# GoodBoy_V1_nRF9160dk_MCU_LTE.net
KiCad netlist of a schematic drawn in Altium Designer
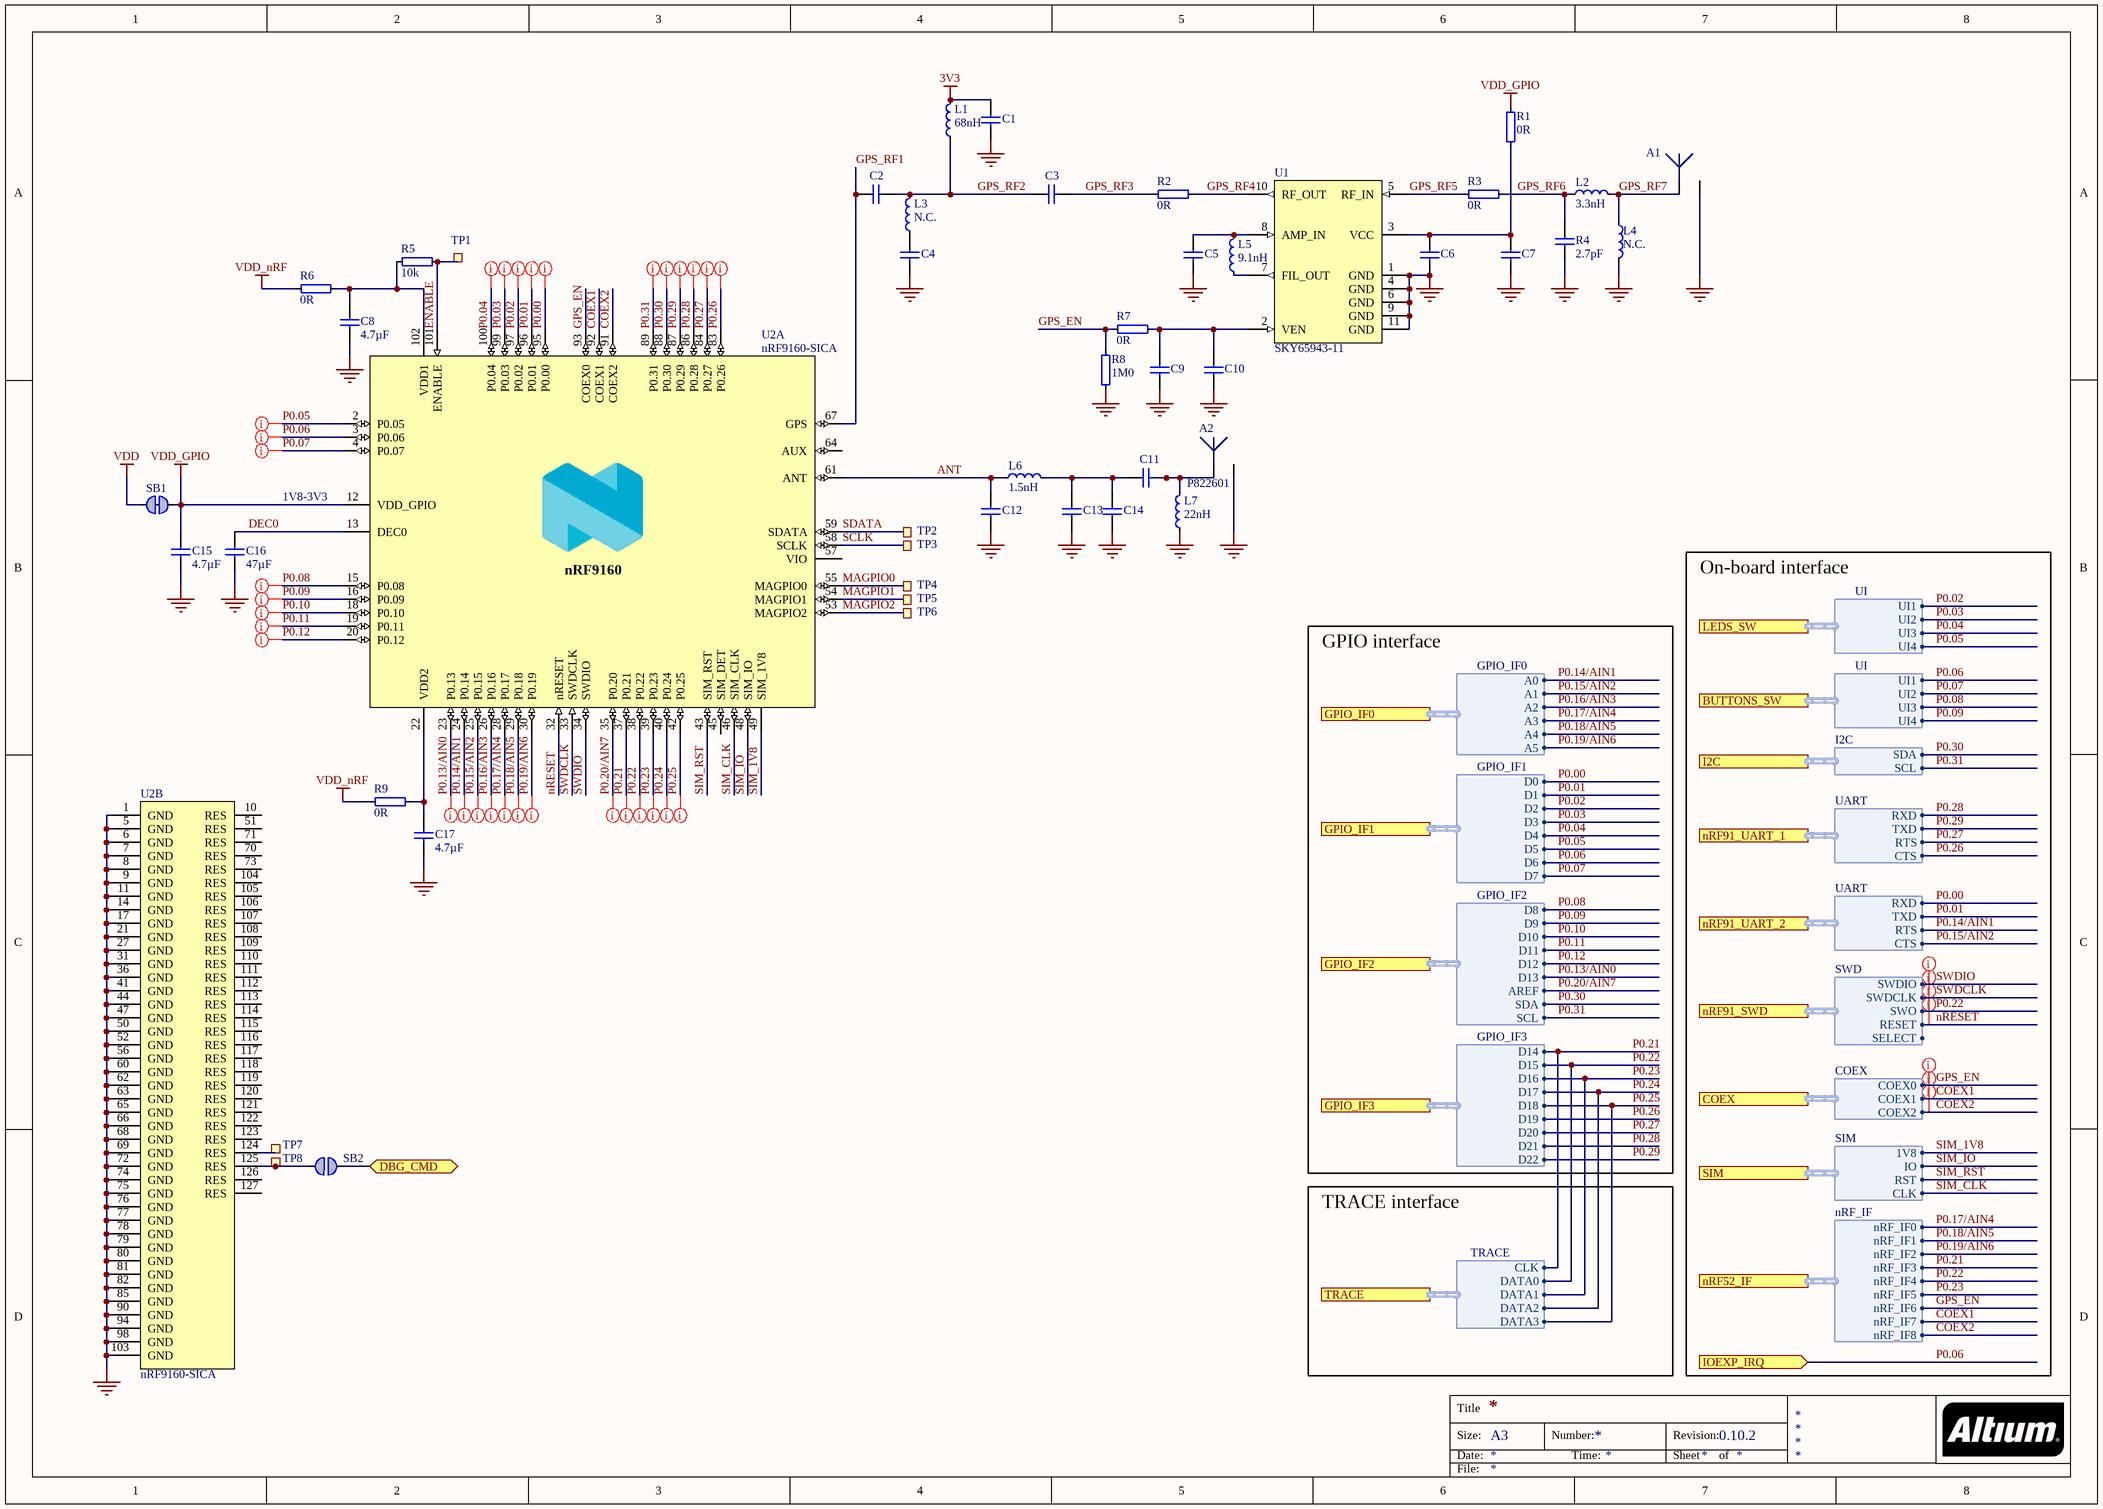
[diagram p0: GoodBoy_V1_nRF9160dk_MCU_LTE.SchDoc]

(export (version "E")
  (design (tool "Eeschema 10.0.6"))
  (components
    (comp (ref "A1")
      (value "~")
      (footprint "ACAG0301-1575-T")
      (description "RF ANT 1.575GHZ CHIP SOLDER SMD")
      (fields
        (field (name "PART NUMBER") "ACAG0301-1575-T")
        (field (name "MANUFACTURER") "Abracon")
        (field (name "PUBLISHER") "Nordic Semiconductor")
      )
      (libsource (lib "pca10090") (part "ACAG0301-1575-T"))
    )
    (comp (ref "A2")
      (value "P822601")
      (footprint "P822601")
      (description "ANTENNA PRESTTA OCTABAND LTE")
      (fields (field (name "MANUFACTURER") "Ethertronics") (field (name "PUBLISHER") "Nordic Semiconductor"))
      (libsource (lib "pca10090") (part "W3796"))
    )
    (comp (ref "C1")
      (value "~")
      (footprint "CAPC0603X03L_C")
      (description "Capacitor, NP0, ±1%, 25V")
      (fields (field (name "PART NUMBER") "C0201-39p") (field (name "PUBLISHER") "Nordic Semiconductor"))
      (libsource (lib "400389") (part "CAP"))
    )
    (comp (ref "C2")
      (value "~")
      (footprint "CAPC0603X03L_C")
      (description "Capacitor, NP0, ±1%, 25V")
      (fields (field (name "PART NUMBER") "C0201-39p") (field (name "PUBLISHER") "Nordic Semiconductor"))
      (libsource (lib "400389") (part "CAP"))
    )
    (comp (ref "C3")
      (value "~")
      (footprint "CAPC0603X03L_C")
      (description "Capacitor, NP0, ±1%, 25V")
      (fields (field (name "PART NUMBER") "C0201-39p") (field (name "PUBLISHER") "Nordic Semiconductor"))
      (libsource (lib "400389") (part "CAP"))
    )
    (comp (ref "C4")
      (value "~")
      (footprint "CAPC0603X03L_C")
      (description "Not mounted")
      (fields (field (name "PART NUMBER") "C0201-N.C.") (field (name "PUBLISHER") "Nordic Semiconductor"))
      (libsource (lib "400389") (part "CAP"))
    )
    (comp (ref "C5")
      (value "~")
      (footprint "CAPC0603X03L_C")
      (description "Not mounted")
      (fields (field (name "PART NUMBER") "C0201-N.C.") (field (name "PUBLISHER") "Nordic Semiconductor"))
      (libsource (lib "400389") (part "CAP"))
    )
    (comp (ref "C6")
      (value "~")
      (footprint "CAPC0603X03L_C")
      (description "Capacitor, NP0, ±2%, 25V")
      (fields (field (name "PART NUMBER") "C0201-100p") (field (name "PUBLISHER") "Nordic Semiconductor"))
      (libsource (lib "400389") (part "CAP"))
    )
    (comp (ref "C7")
      (value "~")
      (footprint "CAPC0603X03L_C")
      (description "Capacitor, X5R, ±10%")
      (fields (field (name "PART NUMBER") "C0201-100n") (field (name "PUBLISHER") "Nordic Semiconductor"))
      (libsource (lib "400389") (part "CAP"))
    )
    (comp (ref "C8")
      (value "4.7µF")
      (footprint "CAPC1005X04L")
      (description "Capacitor, X5R, ±20%")
      (fields (field (name "PART NUMBER") "C0402-4µ7") (field (name "PUBLISHER") "Nordic Semiconductor"))
      (libsource (lib "Nordic Passive DB") (part "CAP"))
    )
    (comp (ref "C9")
      (value "~")
      (footprint "CAPC0603X03L_C")
      (description "Capacitor, X5R, ±10%")
      (fields (field (name "PART NUMBER") "C0201-100n") (field (name "PUBLISHER") "Nordic Semiconductor"))
      (libsource (lib "400389") (part "CAP"))
    )
    (comp (ref "C10")
      (value "~")
      (footprint "CAPC0603X03L_C")
      (description "Capacitor, NP0, ±2%, 25V")
      (fields (field (name "PART NUMBER") "C0201-100p") (field (name "PUBLISHER") "Nordic Semiconductor"))
      (libsource (lib "400389") (part "CAP"))
    )
    (comp (ref "C11")
      (value "~")
      (footprint "CAPC0603X03L_C")
      (description "Capacitor, NP0, ±0.1pF, 25V")
      (fields
        (field (name "PART NUMBER") "C0201-3.5p")
        (field (name "MANUFACTURER") "Murata")
        (field (name "PUBLISHER") "Nordic Semiconductor")
      )
      (libsource (lib "400389") (part "CAP"))
    )
    (comp (ref "C12")
      (value "~")
      (footprint "CAPC0603X03L_C")
      (description "Not mounted")
      (fields (field (name "PART NUMBER") "C0201-N.C.") (field (name "PUBLISHER") "Nordic Semiconductor"))
      (libsource (lib "400389") (part "CAP"))
    )
    (comp (ref "C13")
      (value "~")
      (footprint "CAPC0603X03L_C")
      (description "Not mounted")
      (fields (field (name "PART NUMBER") "C0201-N.C.") (field (name "PUBLISHER") "Nordic Semiconductor"))
      (libsource (lib "400389") (part "CAP"))
    )
    (comp (ref "C14")
      (value "~")
      (footprint "CAPC0603X03L_C")
      (description "Not mounted")
      (fields (field (name "PART NUMBER") "C0201-N.C.") (field (name "PUBLISHER") "Nordic Semiconductor"))
      (libsource (lib "400389") (part "CAP"))
    )
    (comp (ref "C15")
      (value "4.7µF")
      (footprint "CAPC1005X04L")
      (description "Capacitor, X5R, ±20%")
      (fields (field (name "PART NUMBER") "C0402-4µ7") (field (name "PUBLISHER") "Nordic Semiconductor"))
      (libsource (lib "Nordic Passive DB") (part "CAP"))
    )
    (comp (ref "C16")
      (value "47µF")
      (footprint "CAPC2012X11L")
      (description "Capacitor, X5R, ±20%, 6.3V")
      (fields
        (field (name "PART NUMBER") "C0805-47µ")
        (field (name "MANUFACTURER") "Taiyo Yuden")
        (field (name "PUBLISHER") "Nordic Semiconductor")
      )
      (libsource (lib "Nordic Passive DB") (part "CAP"))
    )
    (comp (ref "C17")
      (value "4.7µF")
      (footprint "CAPC1005X04L")
      (description "Capacitor, X5R, ±20%")
      (fields (field (name "PART NUMBER") "C0402-4µ7") (field (name "PUBLISHER") "Nordic Semiconductor"))
      (libsource (lib "Nordic Passive DB") (part "CAP"))
    )
    (comp (ref "L1")
      (value "68nH")
      (footprint "INDC1005X04L_WW")
      (description "Inductor, 140mA, ±2%, 1960mΩ, Q=20")
      (fields
        (field (name "PART NUMBER") "L0402-68n-Wirewound-Murata")
        (field (name "MANUFACTURER") "Murata")
        (field (name "PUBLISHER") "Nordic Semiconductor")
      )
      (libsource (lib "") (part "IND_1"))
    )
    (comp (ref "L2")
      (value "3.3nH")
      (footprint "INDC1005X04L_WW")
      (description "Inductor, 900mA, ±0.5nH, 40mΩ, Q=30")
      (fields
        (field (name "PART NUMBER") "L0402-3n3-Wirewound-Murata")
        (field (name "MANUFACTURER") "Murata")
        (field (name "PUBLISHER") "Nordic Semiconductor")
      )
      (libsource (lib "Nordic Passive DB") (part "IND"))
    )
    (comp (ref "L3")
      (value "N.C.")
      (footprint "INDC1005X04L")
      (description "Not mounted")
      (fields (field (name "PART NUMBER") "L0402-N.C.") (field (name "PUBLISHER") "Nordic Semiconductor"))
      (libsource (lib "") (part "IND_1"))
    )
    (comp (ref "L4")
      (value "N.C.")
      (footprint "INDC1005X04L")
      (description "Not mounted")
      (fields (field (name "PART NUMBER") "L0402-N.C.") (field (name "PUBLISHER") "Nordic Semiconductor"))
      (libsource (lib "Nordic Passive DB") (part "IND"))
    )
    (comp (ref "L5")
      (value "9.1nH")
      (footprint "INDC1005X04L_WW")
      (description "Inductor, 540mA, ±2%, 140mΩ, Q=25")
      (fields
        (field (name "PART NUMBER") "L0402-9n1-Wirewound-Murata")
        (field (name "MANUFACTURER") "Murata")
        (field (name "PUBLISHER") "Nordic Semiconductor")
      )
      (libsource (lib "") (part "IND_1"))
    )
    (comp (ref "L6")
      (value "1.5nH")
      (footprint "INDC0603X03L_C")
      (description "Inductor, 650mA, ±0.1nH")
      (fields
        (field (name "PART NUMBER") "L0201-1n5")
        (field (name "MANUFACTURER") "Murata")
        (field (name "PUBLISHER") "Nordic Semiconductor")
      )
      (libsource (lib "Nordic Passive DB") (part "IND"))
    )
    (comp (ref "L7")
      (value "22nH")
      (footprint "INDC0603X03L_C")
      (description "Chip Inductor")
      (fields (field (name "PART NUMBER") "L0201-22n") (field (name "PUBLISHER") "Nordic Semiconductor"))
      (libsource (lib "Nordic Passive DB") (part "IND"))
    )
    (comp (ref "R1")
      (value "0R")
      (footprint "RESC0603X03L_C")
      (description "Resistor, ±5%, 0.05W")
      (fields (field (name "PART NUMBER") "R0201-0R") (field (name "PUBLISHER") "Nordic Semiconductor"))
      (libsource (lib "Nordic Passive DB") (part "RES_1"))
    )
    (comp (ref "R2")
      (value "0R")
      (footprint "RESC0603X03L_C")
      (description "Resistor, ±5%, 0.05W")
      (fields (field (name "PART NUMBER") "R0201-0R") (field (name "PUBLISHER") "Nordic Semiconductor"))
      (libsource (lib "Nordic Passive DB") (part "RES_1"))
    )
    (comp (ref "R3")
      (value "0R")
      (footprint "RESC0603X03L_C")
      (description "Resistor, ±5%, 0.05W")
      (fields (field (name "PART NUMBER") "R0201-0R") (field (name "PUBLISHER") "Nordic Semiconductor"))
      (libsource (lib "Nordic Passive DB") (part "RES_1"))
    )
    (comp (ref "R4")
      (value "2.7pF")
      (footprint "CAPC1005X04L")
      (description "Chip Cap 0402")
      (fields (field (name "PART NUMBER") "C0402-2.7p") (field (name "PUBLISHER") "Nordic Semiconductor"))
      (libsource (lib "Nordic Passive DB") (part "CAP"))
    )
    (comp (ref "R5")
      (value "10k")
      (footprint "RESC0603X03L_C")
      (description "Resistor, ±1%, 0.05W")
      (fields (field (name "PART NUMBER") "R0201-10k") (field (name "PUBLISHER") "Nordic Semiconductor"))
      (libsource (lib "Nordic Passive DB") (part "RES_1"))
    )
    (comp (ref "R6")
      (value "0R")
      (footprint "RESC0603X03L_C")
      (description "Resistor, ±5%, 0.05W")
      (fields (field (name "PART NUMBER") "R0201-0R") (field (name "PUBLISHER") "Nordic Semiconductor"))
      (libsource (lib "Nordic Passive DB") (part "RES_1"))
    )
    (comp (ref "R7")
      (value "0R")
      (footprint "RESC0603X03L_C")
      (description "Resistor, ±5%, 0.05W")
      (fields (field (name "PART NUMBER") "R0201-0R") (field (name "PUBLISHER") "Nordic Semiconductor"))
      (libsource (lib "Nordic Passive DB") (part "RES_1"))
    )
    (comp (ref "R8")
      (value "1M0")
      (footprint "RESC0603X03L_C")
      (description "Resistor, ±1%, 0.05W")
      (fields (field (name "PART NUMBER") "R0201-1M0") (field (name "PUBLISHER") "Nordic Semiconductor"))
      (libsource (lib "Nordic Passive DB") (part "RES_1"))
    )
    (comp (ref "R9")
      (value "0R")
      (footprint "RESC0603X03L_C")
      (description "Resistor, ±5%, 0.05W")
      (fields (field (name "PART NUMBER") "R0201-0R") (field (name "PUBLISHER") "Nordic Semiconductor"))
      (libsource (lib "Nordic Passive DB") (part "RES_1"))
    )
    (comp (ref "SB1")
      (value "Solderbridge")
      (footprint "Solderbridge_Shorted")
      (description "Shorted Solderbridge")
      (fields
        (field (name "PART NUMBER") "Solderbridge Shorted")
        (field (name "PUBLISHER") "Nordic Semiconductor")
      )
      (libsource (lib "Nordic Passive DB") (part "SOLDERBRIDGE_SHORTED"))
    )
    (comp (ref "SB2")
      (value "Solderbridge")
      (footprint "Solderbridge")
      (fields (field (name "PUBLISHER") "Nordic Semiconductor"))
      (libsource (lib "Nordic Passive DB") (part "SOLDERBRIDGE"))
    )
    (comp (ref "TP1")
      (value "Ø1.5mm,SMD")
      (footprint "TP_SMD_Ø1.5mm")
      (description "1.0mm circular SMD testpad")
      (fields
        (field (name "PART NUMBER") "TP_SMD_Ø1.5MM")
        (field (name "MANUFACTURER") "Nordic Semiconductor")
        (field (name "PUBLISHER") "Nordic Semiconductor")
      )
      (libsource (lib "Nordic Passive DB") (part "TESTPAD"))
    )
    (comp (ref "TP2")
      (value "Ø1.0mm,SMD")
      (footprint "TP_SMD_Ø1.0mm")
      (description "1.0mm circular SMD testpad")
      (fields
        (field (name "PART NUMBER") "TP_SMD_Ø1.0MM")
        (field (name "MANUFACTURER") "Nordic Semiconductor")
        (field (name "PUBLISHER") "Nordic Semiconductor")
      )
      (libsource (lib "") (part "TESTPAD_1"))
    )
    (comp (ref "TP3")
      (value "Ø1.0mm,SMD")
      (footprint "TP_SMD_Ø1.0mm")
      (description "1.0mm circular SMD testpad")
      (fields
        (field (name "PART NUMBER") "TP_SMD_Ø1.0MM")
        (field (name "MANUFACTURER") "Nordic Semiconductor")
        (field (name "PUBLISHER") "Nordic Semiconductor")
      )
      (libsource (lib "") (part "TESTPAD_1"))
    )
    (comp (ref "TP4")
      (value "Ø1.0mm,SMD")
      (footprint "TP_SMD_Ø1.0mm")
      (description "1.0mm circular SMD testpad")
      (fields
        (field (name "PART NUMBER") "TP_SMD_Ø1.0MM")
        (field (name "MANUFACTURER") "Nordic Semiconductor")
        (field (name "PUBLISHER") "Nordic Semiconductor")
      )
      (libsource (lib "") (part "TESTPAD_1"))
    )
    (comp (ref "TP5")
      (value "Ø1.0mm,SMD")
      (footprint "TP_SMD_Ø1.0mm")
      (description "1.0mm circular SMD testpad")
      (fields
        (field (name "PART NUMBER") "TP_SMD_Ø1.0MM")
        (field (name "MANUFACTURER") "Nordic Semiconductor")
        (field (name "PUBLISHER") "Nordic Semiconductor")
      )
      (libsource (lib "") (part "TESTPAD_1"))
    )
    (comp (ref "TP6")
      (value "Ø1.0mm,SMD")
      (footprint "TP_SMD_Ø1.0mm")
      (description "1.0mm circular SMD testpad")
      (fields
        (field (name "PART NUMBER") "TP_SMD_Ø1.0MM")
        (field (name "MANUFACTURER") "Nordic Semiconductor")
        (field (name "PUBLISHER") "Nordic Semiconductor")
      )
      (libsource (lib "") (part "TESTPAD_1"))
    )
    (comp (ref "TP7")
      (value "Ø1.0mm,SMD")
      (footprint "TP_SMD_Ø1.0mm")
      (description "1.0mm circular SMD testpad")
      (fields
        (field (name "PART NUMBER") "TP_SMD_Ø1.0MM")
        (field (name "MANUFACTURER") "Nordic Semiconductor")
        (field (name "PUBLISHER") "Nordic Semiconductor")
      )
      (libsource (lib "Nordic Passive DB") (part "TESTPAD"))
    )
    (comp (ref "TP8")
      (value "Ø1.0mm,SMD")
      (footprint "TP_SMD_Ø1.0mm")
      (description "1.0mm circular SMD testpad")
      (fields
        (field (name "PART NUMBER") "TP_SMD_Ø1.0MM")
        (field (name "MANUFACTURER") "Nordic Semiconductor")
        (field (name "PUBLISHER") "Nordic Semiconductor")
      )
      (libsource (lib "Nordic Passive DB") (part "TESTPAD"))
    )
    (comp (ref "U1")
      (value "SKY65943-11")
      (footprint "SKY65943-11")
      (description "GNSS Low-Noise Amplifier Front-End Module with Integrated Pre-Filter and Post-Filter")
      (fields (field (name "MANUFACTURER") "Skyworks") (field (name "PUBLISHER") "Nordic Semiconductor"))
      (libsource (lib "pca10090") (part "SKY65943-11"))
    )
    (comp (ref "U2")
      (value "nRF9160-SICA")
      (footprint "LGA50P1600X1050X104-161N")
      (description "Low power System-in-Package with integrated LTE-M/NB-IoT modem and GPS")
      (fields
        (field (name "PART NUMBER") "nRF9160-SICAB00")
        (field (name "MANUFACTURER") "Nordic Semiconductor")
        (field (name "PUBLISHER") "Nordic Semiconductor")
      )
      (libsource (lib "pca10090") (part "nRF9160_SICA"))
    )
  )
  (nets
    (net (code "13") (name "/ANT") (class "Default")
      (node (ref "C12") (pin "2") (pinfunction "2_2") (pintype "passive"))
      (node (ref "L6") (pin "1") (pinfunction "1_1") (pintype "passive"))
      (node (ref "U2") (pin "61") (pinfunction "ANT_61") (pintype "bidirectional"))
    )
    (net (code "14") (name "/COEX1") (class "Default")
      (node (ref "U2") (pin "92") (pinfunction "COEX1_92") (pintype "bidirectional"))
    )
    (net (code "15") (name "/COEX2") (class "Default")
      (node (ref "U2") (pin "91") (pinfunction "COEX2_91") (pintype "bidirectional"))
    )
    (net (code "16") (name "/DBG_CMD") (class "Default")
      (node (ref "SB2") (pin "1") (pinfunction "0_1") (pintype "passive"))
    )
    (net (code "17") (name "/DEC0") (class "Default")
      (node (ref "C16") (pin "1") (pinfunction "1_1") (pintype "passive"))
      (node (ref "U2") (pin "13") (pinfunction "DEC0_13") (pintype "power_in"))
    )
    (net (code "18") (name "/ENABLE") (class "Default")
      (node (ref "R5") (pin "2") (pinfunction "2_2") (pintype "passive"))
      (node (ref "TP1") (pin "1") (pinfunction "1_1") (pintype "passive"))
      (node (ref "U2") (pin "101") (pinfunction "ENABLE_101") (pintype "input"))
    )
    (net (code "19") (name "/GPS_EN") (class "Default")
      (node (ref "R7") (pin "1") (pinfunction "1_1") (pintype "passive"))
      (node (ref "R8") (pin "2") (pinfunction "2_2") (pintype "passive"))
      (node (ref "U2") (pin "93") (pinfunction "COEX0_93") (pintype "bidirectional"))
    )
    (net (code "20") (name "/GPS_RF1") (class "Default")
      (node (ref "C2") (pin "2") (pinfunction "2_2") (pintype "passive"))
      (node (ref "U2") (pin "67") (pinfunction "GPS_67") (pintype "bidirectional"))
    )
    (net (code "21") (name "/GPS_RF2") (class "Default")
      (node (ref "C2") (pin "1") (pinfunction "1_1") (pintype "passive"))
      (node (ref "C3") (pin "2") (pinfunction "2_2") (pintype "passive"))
      (node (ref "L1") (pin "2") (pinfunction "2_2") (pintype "passive"))
      (node (ref "L3") (pin "1") (pinfunction "1_1") (pintype "passive"))
    )
    (net (code "22") (name "/GPS_RF3") (class "Default")
      (node (ref "C3") (pin "1") (pinfunction "1_1") (pintype "passive"))
      (node (ref "R2") (pin "1") (pinfunction "1_1") (pintype "passive"))
    )
    (net (code "23") (name "/GPS_RF4") (class "Default")
      (node (ref "R2") (pin "2") (pinfunction "2_2") (pintype "passive"))
      (node (ref "U1") (pin "10") (pinfunction "RF_OUT_10") (pintype "output"))
    )
    (net (code "24") (name "/GPS_RF5") (class "Default")
      (node (ref "R3") (pin "1") (pinfunction "1_1") (pintype "passive"))
      (node (ref "U1") (pin "5") (pinfunction "RF_IN_5") (pintype "input"))
    )
    (net (code "25") (name "/GPS_RF6") (class "Default")
      (node (ref "L2") (pin "1") (pinfunction "1_1") (pintype "passive"))
      (node (ref "R3") (pin "2") (pinfunction "2_2") (pintype "passive"))
      (node (ref "R4") (pin "1") (pinfunction "1_1") (pintype "passive"))
    )
    (net (code "26") (name "/GPS_RF7") (class "Default")
      (node (ref "A1") (pin "1") (pintype "passive"))
      (node (ref "L2") (pin "2") (pinfunction "2_2") (pintype "passive"))
      (node (ref "L4") (pin "1") (pinfunction "1_1") (pintype "passive"))
    )
    (net (code "27") (name "/MAGPIO0") (class "Default")
      (node (ref "TP4") (pin "1") (pinfunction "1_1") (pintype "passive"))
      (node (ref "U2") (pin "55") (pinfunction "MAGPIO0_55") (pintype "bidirectional"))
    )
    (net (code "28") (name "/MAGPIO1") (class "Default")
      (node (ref "TP5") (pin "1") (pinfunction "1_1") (pintype "passive"))
      (node (ref "U2") (pin "54") (pinfunction "MAGPIO1_54") (pintype "bidirectional"))
    )
    (net (code "29") (name "/MAGPIO2") (class "Default")
      (node (ref "TP6") (pin "1") (pinfunction "1_1") (pintype "passive"))
      (node (ref "U2") (pin "53") (pinfunction "MAGPIO2_53") (pintype "bidirectional"))
    )
    (net (code "30") (name "/P0.00") (class "Default")
      (node (ref "U2") (pin "95") (pinfunction "P0.00_95") (pintype "bidirectional"))
    )
    (net (code "31") (name "/P0.01") (class "Default")
      (node (ref "U2") (pin "96") (pinfunction "P0.01_96") (pintype "bidirectional"))
    )
    (net (code "32") (name "/P0.02") (class "Default")
      (node (ref "U2") (pin "97") (pinfunction "P0.02_97") (pintype "bidirectional"))
    )
    (net (code "33") (name "/P0.03") (class "Default")
      (node (ref "U2") (pin "99") (pinfunction "P0.03_99") (pintype "bidirectional"))
    )
    (net (code "34") (name "/P0.04") (class "Default")
      (node (ref "U2") (pin "100") (pinfunction "P0.04_100") (pintype "bidirectional"))
    )
    (net (code "35") (name "/P0.05") (class "Default")
      (node (ref "U2") (pin "2") (pinfunction "P0.05_2") (pintype "bidirectional"))
    )
    (net (code "36") (name "/P0.06") (class "Default")
      (node (ref "U2") (pin "3") (pinfunction "P0.06_3") (pintype "bidirectional"))
    )
    (net (code "37") (name "/P0.07") (class "Default")
      (node (ref "U2") (pin "4") (pinfunction "P0.07_4") (pintype "bidirectional"))
    )
    (net (code "38") (name "/P0.08") (class "Default")
      (node (ref "U2") (pin "15") (pinfunction "P0.08_15") (pintype "bidirectional"))
    )
    (net (code "39") (name "/P0.09") (class "Default")
      (node (ref "U2") (pin "16") (pinfunction "P0.09_16") (pintype "bidirectional"))
    )
    (net (code "40") (name "/P0.10") (class "Default")
      (node (ref "U2") (pin "18") (pinfunction "P0.10_18") (pintype "bidirectional"))
    )
    (net (code "41") (name "/P0.11") (class "Default")
      (node (ref "U2") (pin "19") (pinfunction "P0.11_19") (pintype "bidirectional"))
    )
    (net (code "42") (name "/P0.12") (class "Default")
      (node (ref "U2") (pin "20") (pinfunction "P0.12_20") (pintype "bidirectional"))
    )
    (net (code "43") (name "/P0.13{slash}AIN0") (class "Default")
      (node (ref "U2") (pin "23") (pinfunction "P0.13_23") (pintype "bidirectional"))
    )
    (net (code "44") (name "/P0.14{slash}AIN1") (class "Default")
      (node (ref "U2") (pin "24") (pinfunction "P0.14_24") (pintype "bidirectional"))
    )
    (net (code "45") (name "/P0.15{slash}AIN2") (class "Default")
      (node (ref "U2") (pin "25") (pinfunction "P0.15_25") (pintype "bidirectional"))
    )
    (net (code "46") (name "/P0.16{slash}AIN3") (class "Default")
      (node (ref "U2") (pin "26") (pinfunction "P0.16_26") (pintype "bidirectional"))
    )
    (net (code "47") (name "/P0.17{slash}AIN4") (class "Default")
      (node (ref "U2") (pin "28") (pinfunction "P0.17_28") (pintype "bidirectional"))
    )
    (net (code "48") (name "/P0.18{slash}AIN5") (class "Default")
      (node (ref "U2") (pin "29") (pinfunction "P0.18_29") (pintype "bidirectional"))
    )
    (net (code "49") (name "/P0.19{slash}AIN6") (class "Default")
      (node (ref "U2") (pin "30") (pinfunction "P0.19_30") (pintype "bidirectional"))
    )
    (net (code "50") (name "/P0.20{slash}AIN7") (class "Default")
      (node (ref "U2") (pin "35") (pinfunction "P0.20_35") (pintype "bidirectional"))
    )
    (net (code "51") (name "/P0.21") (class "Default")
      (node (ref "U2") (pin "37") (pinfunction "P0.21_37") (pintype "bidirectional"))
    )
    (net (code "52") (name "/P0.22") (class "Default")
      (node (ref "U2") (pin "38") (pinfunction "P0.22_38") (pintype "bidirectional"))
    )
    (net (code "53") (name "/P0.23") (class "Default")
      (node (ref "U2") (pin "39") (pinfunction "P0.23_39") (pintype "bidirectional"))
    )
    (net (code "54") (name "/P0.24") (class "Default")
      (node (ref "U2") (pin "40") (pinfunction "P0.24_40") (pintype "bidirectional"))
    )
    (net (code "55") (name "/P0.25") (class "Default")
      (node (ref "U2") (pin "42") (pinfunction "P0.25_42") (pintype "bidirectional"))
    )
    (net (code "56") (name "/P0.26") (class "Default")
      (node (ref "U2") (pin "83") (pinfunction "P0.26_83") (pintype "bidirectional"))
    )
    (net (code "57") (name "/P0.27") (class "Default")
      (node (ref "U2") (pin "84") (pinfunction "P0.27_84") (pintype "bidirectional"))
    )
    (net (code "58") (name "/P0.28") (class "Default")
      (node (ref "U2") (pin "86") (pinfunction "P0.28_86") (pintype "bidirectional"))
    )
    (net (code "59") (name "/P0.29") (class "Default")
      (node (ref "U2") (pin "87") (pinfunction "P0.29_87") (pintype "bidirectional"))
    )
    (net (code "60") (name "/P0.30") (class "Default")
      (node (ref "U2") (pin "88") (pinfunction "P0.30_88") (pintype "bidirectional"))
    )
    (net (code "61") (name "/P0.31") (class "Default")
      (node (ref "U2") (pin "89") (pinfunction "P0.31_89") (pintype "bidirectional"))
    )
    (net (code "62") (name "/SCLK") (class "Default")
      (node (ref "TP3") (pin "1") (pinfunction "1_1") (pintype "passive"))
      (node (ref "U2") (pin "58") (pinfunction "SCLK_58") (pintype "bidirectional"))
    )
    (net (code "63") (name "/SDATA") (class "Default")
      (node (ref "TP2") (pin "1") (pinfunction "1_1") (pintype "passive"))
      (node (ref "U2") (pin "59") (pinfunction "SDATA_59") (pintype "bidirectional"))
    )
    (net (code "64") (name "/SIM_1V8") (class "Default")
      (node (ref "U2") (pin "49") (pinfunction "SIM_1V8_49") (pintype "power_in"))
    )
    (net (code "65") (name "/SIM_CLK") (class "Default")
      (node (ref "U2") (pin "46") (pinfunction "SIM_CLK_46") (pintype "bidirectional"))
    )
    (net (code "66") (name "/SIM_IO") (class "Default")
      (node (ref "U2") (pin "48") (pinfunction "SIM_IO_48") (pintype "bidirectional"))
    )
    (net (code "67") (name "/SIM_RST") (class "Default")
      (node (ref "U2") (pin "43") (pinfunction "SIM_RST_43") (pintype "bidirectional"))
    )
    (net (code "68") (name "/SWDCLK") (class "Default")
      (node (ref "U2") (pin "33") (pinfunction "SWDCLK_33") (pintype "input"))
    )
    (net (code "69") (name "/SWDIO") (class "Default")
      (node (ref "U2") (pin "34") (pinfunction "SWDIO_34") (pintype "bidirectional"))
    )
    (net (code "70") (name "/nRESET") (class "Default")
      (node (ref "U2") (pin "32") (pinfunction "nRESET_32") (pintype "input"))
    )
    (net (code "83") (name "3V3") (class "Default")
      (node (ref "C1") (pin "2") (pinfunction "2_2") (pintype "passive"))
      (node (ref "L1") (pin "1") (pinfunction "1_1") (pintype "passive"))
    )
    (net (code "84") (name "GND") (class "Default")
      (node (ref "A1") (pin "2") (pintype "passive"))
      (node (ref "A2") (pin "2") (pintype "passive"))
      (node (ref "C1") (pin "1") (pinfunction "1_1") (pintype "passive"))
      (node (ref "C10") (pin "1") (pinfunction "1_1") (pintype "passive"))
      (node (ref "C12") (pin "1") (pinfunction "1_1") (pintype "passive"))
      (node (ref "C13") (pin "1") (pinfunction "1_1") (pintype "passive"))
      (node (ref "C14") (pin "1") (pinfunction "1_1") (pintype "passive"))
      (node (ref "C15") (pin "2") (pinfunction "2_2") (pintype "passive"))
      (node (ref "C16") (pin "2") (pinfunction "2_2") (pintype "passive"))
      (node (ref "C17") (pin "1") (pinfunction "1_1") (pintype "passive"))
      (node (ref "C4") (pin "1") (pinfunction "1_1") (pintype "passive"))
      (node (ref "C5") (pin "2") (pinfunction "2_2") (pintype "passive"))
      (node (ref "C6") (pin "1") (pinfunction "1_1") (pintype "passive"))
      (node (ref "C7") (pin "1") (pinfunction "1_1") (pintype "passive"))
      (node (ref "C8") (pin "2") (pinfunction "2_2") (pintype "passive"))
      (node (ref "C9") (pin "1") (pinfunction "1_1") (pintype "passive"))
      (node (ref "L4") (pin "2") (pinfunction "2_2") (pintype "passive"))
      (node (ref "L7") (pin "1") (pinfunction "1_1") (pintype "passive"))
      (node (ref "R4") (pin "2") (pinfunction "2_2") (pintype "passive"))
      (node (ref "R8") (pin "1") (pinfunction "1_1") (pintype "passive"))
      (node (ref "U1") (pin "1") (pinfunction "GND_1") (pintype "power_in"))
      (node (ref "U1") (pin "11") (pinfunction "GND_11") (pintype "power_in"))
      (node (ref "U1") (pin "4") (pinfunction "GND_4") (pintype "power_in"))
      (node (ref "U1") (pin "6") (pinfunction "GND_6") (pintype "power_in"))
      (node (ref "U1") (pin "9") (pinfunction "GND_9") (pintype "power_in"))
      (node (ref "U2") (pin "1") (pinfunction "GND_1") (pintype "power_in"))
      (node (ref "U2") (pin "103") (pinfunction "GND_103") (pintype "power_in"))
      (node (ref "U2") (pin "11") (pinfunction "GND_11") (pintype "passive"))
      (node (ref "U2") (pin "14") (pinfunction "GND_14") (pintype "power_in"))
      (node (ref "U2") (pin "17") (pinfunction "GND_17") (pintype "power_in"))
      (node (ref "U2") (pin "21") (pinfunction "GND_21") (pintype "power_in"))
      (node (ref "U2") (pin "27") (pinfunction "GND_27") (pintype "power_in"))
      (node (ref "U2") (pin "31") (pinfunction "GND_31") (pintype "power_in"))
      (node (ref "U2") (pin "36") (pinfunction "GND_36") (pintype "power_in"))
      (node (ref "U2") (pin "41") (pinfunction "GND_41") (pintype "power_in"))
      (node (ref "U2") (pin "44") (pinfunction "GND_44") (pintype "power_in"))
      (node (ref "U2") (pin "47") (pinfunction "GND_47") (pintype "power_in"))
      (node (ref "U2") (pin "5") (pinfunction "GND_5") (pintype "power_in"))
      (node (ref "U2") (pin "50") (pinfunction "GND_50") (pintype "power_in"))
      (node (ref "U2") (pin "52") (pinfunction "GND_52") (pintype "power_in"))
      (node (ref "U2") (pin "56") (pinfunction "GND_56") (pintype "power_in"))
      (node (ref "U2") (pin "6") (pinfunction "GND_6") (pintype "passive"))
      (node (ref "U2") (pin "60") (pinfunction "GND_60") (pintype "power_in"))
      (node (ref "U2") (pin "62") (pinfunction "GND_62") (pintype "power_in"))
      (node (ref "U2") (pin "63") (pinfunction "GND_63") (pintype "power_in"))
      (node (ref "U2") (pin "65") (pinfunction "GND_65") (pintype "power_in"))
      (node (ref "U2") (pin "66") (pinfunction "GND_66") (pintype "power_in"))
      (node (ref "U2") (pin "68") (pinfunction "GND_68") (pintype "passive"))
      (node (ref "U2") (pin "69") (pinfunction "GND_69") (pintype "passive"))
      (node (ref "U2") (pin "7") (pinfunction "GND_7") (pintype "passive"))
      (node (ref "U2") (pin "72") (pinfunction "GND_72") (pintype "power_in"))
      (node (ref "U2") (pin "74") (pinfunction "GND_74") (pintype "power_in"))
      (node (ref "U2") (pin "75") (pinfunction "GND_75") (pintype "power_in"))
      (node (ref "U2") (pin "76") (pinfunction "GND_76") (pintype "power_in"))
      (node (ref "U2") (pin "77") (pinfunction "GND_77") (pintype "power_in"))
      (node (ref "U2") (pin "78") (pinfunction "GND_78") (pintype "power_in"))
      (node (ref "U2") (pin "79") (pinfunction "GND_79") (pintype "power_in"))
      (node (ref "U2") (pin "8") (pinfunction "GND_8") (pintype "passive"))
      (node (ref "U2") (pin "80") (pinfunction "GND_80") (pintype "power_in"))
      (node (ref "U2") (pin "81") (pinfunction "GND_81") (pintype "power_in"))
      (node (ref "U2") (pin "82") (pinfunction "GND_82") (pintype "power_in"))
      (node (ref "U2") (pin "85") (pinfunction "GND_85") (pintype "power_in"))
      (node (ref "U2") (pin "9") (pinfunction "GND_9") (pintype "power_in"))
      (node (ref "U2") (pin "90") (pinfunction "GND_90") (pintype "power_in"))
      (node (ref "U2") (pin "94") (pinfunction "GND_94") (pintype "power_in"))
      (node (ref "U2") (pin "98") (pinfunction "GND_98") (pintype "power_in"))
    )
    (net (code "85") (name "Net-(A2-Pad1)") (class "Default")
      (node (ref "A2") (pin "1") (pintype "passive"))
      (node (ref "C11") (pin "2") (pinfunction "2_2") (pintype "passive"))
      (node (ref "L7") (pin "2") (pinfunction "2_2") (pintype "passive"))
    )
    (net (code "86") (name "Net-(C4-Pad2)") (class "Default")
      (node (ref "C4") (pin "2") (pinfunction "2_2") (pintype "passive"))
      (node (ref "L3") (pin "2") (pinfunction "2_2") (pintype "passive"))
    )
    (net (code "87") (name "Net-(C11-Pad1)") (class "Default")
      (node (ref "C11") (pin "1") (pinfunction "1_1") (pintype "passive"))
      (node (ref "C13") (pin "2") (pinfunction "2_2") (pintype "passive"))
      (node (ref "C14") (pin "2") (pinfunction "2_2") (pintype "passive"))
      (node (ref "L6") (pin "2") (pinfunction "2_2") (pintype "passive"))
    )
    (net (code "88") (name "Net-(SB2-1)") (class "Default")
      (node (ref "SB2") (pin "2") (pinfunction "1_2") (pintype "passive"))
      (node (ref "TP8") (pin "1") (pinfunction "1_1") (pintype "passive"))
      (node (ref "U2") (pin "125") (pinfunction "RES_125") (pintype "passive"))
    )
    (net (code "89") (name "Net-(TP7-Pad1)") (class "Default")
      (node (ref "TP7") (pin "1") (pinfunction "1_1") (pintype "passive"))
      (node (ref "U2") (pin "124") (pinfunction "RES_124") (pintype "passive"))
    )
    (net (code "90") (name "Net-(U1-AMP_IN)") (class "Default")
      (node (ref "C5") (pin "1") (pinfunction "1_1") (pintype "passive"))
      (node (ref "L5") (pin "1") (pinfunction "1_1") (pintype "passive"))
      (node (ref "U1") (pin "8") (pinfunction "AMP_IN_8") (pintype "input"))
    )
    (net (code "91") (name "Net-(U1-FIL_OUT)") (class "Default")
      (node (ref "L5") (pin "2") (pinfunction "2_2") (pintype "passive"))
      (node (ref "U1") (pin "7") (pinfunction "FIL_OUT_7") (pintype "output"))
    )
    (net (code "92") (name "Net-(U1-VCC)") (class "Default")
      (node (ref "C6") (pin "2") (pinfunction "2_2") (pintype "passive"))
      (node (ref "C7") (pin "2") (pinfunction "2_2") (pintype "passive"))
      (node (ref "R1") (pin "1") (pinfunction "1_1") (pintype "passive"))
      (node (ref "U1") (pin "3") (pinfunction "VCC_3") (pintype "power_in"))
    )
    (net (code "93") (name "Net-(U1-VEN)") (class "Default")
      (node (ref "C10") (pin "2") (pinfunction "2_2") (pintype "passive"))
      (node (ref "C9") (pin "2") (pinfunction "2_2") (pintype "passive"))
      (node (ref "R7") (pin "2") (pinfunction "2_2") (pintype "passive"))
      (node (ref "U1") (pin "2") (pinfunction "VEN_2") (pintype "input"))
    )
    (net (code "94") (name "Net-(U2A-VDD1)") (class "Default")
      (node (ref "C8") (pin "1") (pinfunction "1_1") (pintype "passive"))
      (node (ref "R5") (pin "1") (pinfunction "1_1") (pintype "passive"))
      (node (ref "R6") (pin "2") (pinfunction "2_2") (pintype "passive"))
      (node (ref "U2") (pin "102") (pinfunction "VDD1_102") (pintype "power_in"))
    )
    (net (code "95") (name "Net-(U2A-VDD2)") (class "Default")
      (node (ref "C17") (pin "2") (pinfunction "2_2") (pintype "passive"))
      (node (ref "R9") (pin "2") (pinfunction "2_2") (pintype "passive"))
      (node (ref "U2") (pin "22") (pinfunction "VDD2_22") (pintype "power_in"))
    )
    (net (code "96") (name "VDD") (class "Default")
      (node (ref "SB1") (pin "1") (pinfunction "0_1") (pintype "passive"))
    )
    (net (code "97") (name "VDD_GPIO") (class "Default")
      (node (ref "C15") (pin "1") (pinfunction "1_1") (pintype "passive"))
      (node (ref "R1") (pin "2") (pinfunction "2_2") (pintype "passive"))
      (node (ref "SB1") (pin "2") (pinfunction "1_2") (pintype "passive"))
      (node (ref "U2") (pin "12") (pinfunction "VDD_GPIO_12") (pintype "power_in"))
    )
    (net (code "98") (name "VDD_nRF") (class "Default")
      (node (ref "R6") (pin "1") (pinfunction "1_1") (pintype "passive"))
      (node (ref "R9") (pin "1") (pinfunction "1_1") (pintype "passive"))
    )
    (net (code "99") (name "unconnected-(U2A-AUX-Pad64)") (class "Default")
      (node (ref "U2") (pin "64") (pinfunction "AUX_64") (pintype "bidirectional"))
    )
    (net (code "100") (name "unconnected-(U2A-SIM_DET-Pad45)") (class "Default")
      (node (ref "U2") (pin "45") (pinfunction "SIM_DET_45") (pintype "bidirectional"))
    )
    (net (code "101") (name "unconnected-(U2A-VIO-Pad57)") (class "Default")
      (node (ref "U2") (pin "57") (pinfunction "VIO_57") (pintype "power_in"))
    )
    (net (code "102") (name "unconnected-(U2B-RES-Pad10)") (class "Default")
      (node (ref "U2") (pin "10") (pinfunction "RES_10") (pintype "passive"))
    )
    (net (code "103") (name "unconnected-(U2B-RES-Pad51)") (class "Default")
      (node (ref "U2") (pin "51") (pinfunction "RES_51") (pintype "passive"))
    )
    (net (code "104") (name "unconnected-(U2B-RES-Pad70)") (class "Default")
      (node (ref "U2") (pin "70") (pinfunction "RES_70") (pintype "passive"))
    )
    (net (code "105") (name "unconnected-(U2B-RES-Pad71)") (class "Default")
      (node (ref "U2") (pin "71") (pinfunction "RES_71") (pintype "passive"))
    )
    (net (code "106") (name "unconnected-(U2B-RES-Pad73)") (class "Default")
      (node (ref "U2") (pin "73") (pinfunction "RES_73") (pintype "passive"))
    )
    (net (code "107") (name "unconnected-(U2B-RES-Pad104)") (class "Default")
      (node (ref "U2") (pin "104") (pinfunction "RES_104") (pintype "passive"))
    )
    (net (code "108") (name "unconnected-(U2B-RES-Pad105)") (class "Default")
      (node (ref "U2") (pin "105") (pinfunction "RES_105") (pintype "passive"))
    )
    (net (code "109") (name "unconnected-(U2B-RES-Pad106)") (class "Default")
      (node (ref "U2") (pin "106") (pinfunction "RES_106") (pintype "passive"))
    )
    (net (code "110") (name "unconnected-(U2B-RES-Pad107)") (class "Default")
      (node (ref "U2") (pin "107") (pinfunction "RES_107") (pintype "passive"))
    )
    (net (code "111") (name "unconnected-(U2B-RES-Pad108)") (class "Default")
      (node (ref "U2") (pin "108") (pinfunction "RES_108") (pintype "passive"))
    )
    (net (code "112") (name "unconnected-(U2B-RES-Pad109)") (class "Default")
      (node (ref "U2") (pin "109") (pinfunction "RES_109") (pintype "passive"))
    )
    (net (code "113") (name "unconnected-(U2B-RES-Pad110)") (class "Default")
      (node (ref "U2") (pin "110") (pinfunction "RES_110") (pintype "passive"))
    )
    (net (code "114") (name "unconnected-(U2B-RES-Pad111)") (class "Default")
      (node (ref "U2") (pin "111") (pinfunction "RES_111") (pintype "passive"))
    )
    (net (code "115") (name "unconnected-(U2B-RES-Pad112)") (class "Default")
      (node (ref "U2") (pin "112") (pinfunction "RES_112") (pintype "passive"))
    )
    (net (code "116") (name "unconnected-(U2B-RES-Pad113)") (class "Default")
      (node (ref "U2") (pin "113") (pinfunction "RES_113") (pintype "passive"))
    )
    (net (code "117") (name "unconnected-(U2B-RES-Pad114)") (class "Default")
      (node (ref "U2") (pin "114") (pinfunction "RES_114") (pintype "passive"))
    )
    (net (code "118") (name "unconnected-(U2B-RES-Pad115)") (class "Default")
      (node (ref "U2") (pin "115") (pinfunction "RES_115") (pintype "passive"))
    )
    (net (code "119") (name "unconnected-(U2B-RES-Pad116)") (class "Default")
      (node (ref "U2") (pin "116") (pinfunction "RES_116") (pintype "passive"))
    )
    (net (code "120") (name "unconnected-(U2B-RES-Pad117)") (class "Default")
      (node (ref "U2") (pin "117") (pinfunction "RES_117") (pintype "passive"))
    )
    (net (code "121") (name "unconnected-(U2B-RES-Pad118)") (class "Default")
      (node (ref "U2") (pin "118") (pinfunction "RES_118") (pintype "passive"))
    )
    (net (code "122") (name "unconnected-(U2B-RES-Pad119)") (class "Default")
      (node (ref "U2") (pin "119") (pinfunction "RES_119") (pintype "passive"))
    )
    (net (code "123") (name "unconnected-(U2B-RES-Pad120)") (class "Default")
      (node (ref "U2") (pin "120") (pinfunction "RES_120") (pintype "passive"))
    )
    (net (code "124") (name "unconnected-(U2B-RES-Pad121)") (class "Default")
      (node (ref "U2") (pin "121") (pinfunction "RES_121") (pintype "passive"))
    )
    (net (code "125") (name "unconnected-(U2B-RES-Pad122)") (class "Default")
      (node (ref "U2") (pin "122") (pinfunction "RES_122") (pintype "passive"))
    )
    (net (code "126") (name "unconnected-(U2B-RES-Pad123)") (class "Default")
      (node (ref "U2") (pin "123") (pinfunction "RES_123") (pintype "passive"))
    )
    (net (code "127") (name "unconnected-(U2B-RES-Pad126)") (class "Default")
      (node (ref "U2") (pin "126") (pinfunction "RES_126") (pintype "passive"))
    )
    (net (code "128") (name "unconnected-(U2B-RES-Pad127)") (class "Default")
      (node (ref "U2") (pin "127") (pinfunction "RES_127") (pintype "passive"))
    )
  )
)
